# MP3_Shield.net
KiCad netlist of a schematic drawn in EAGLE
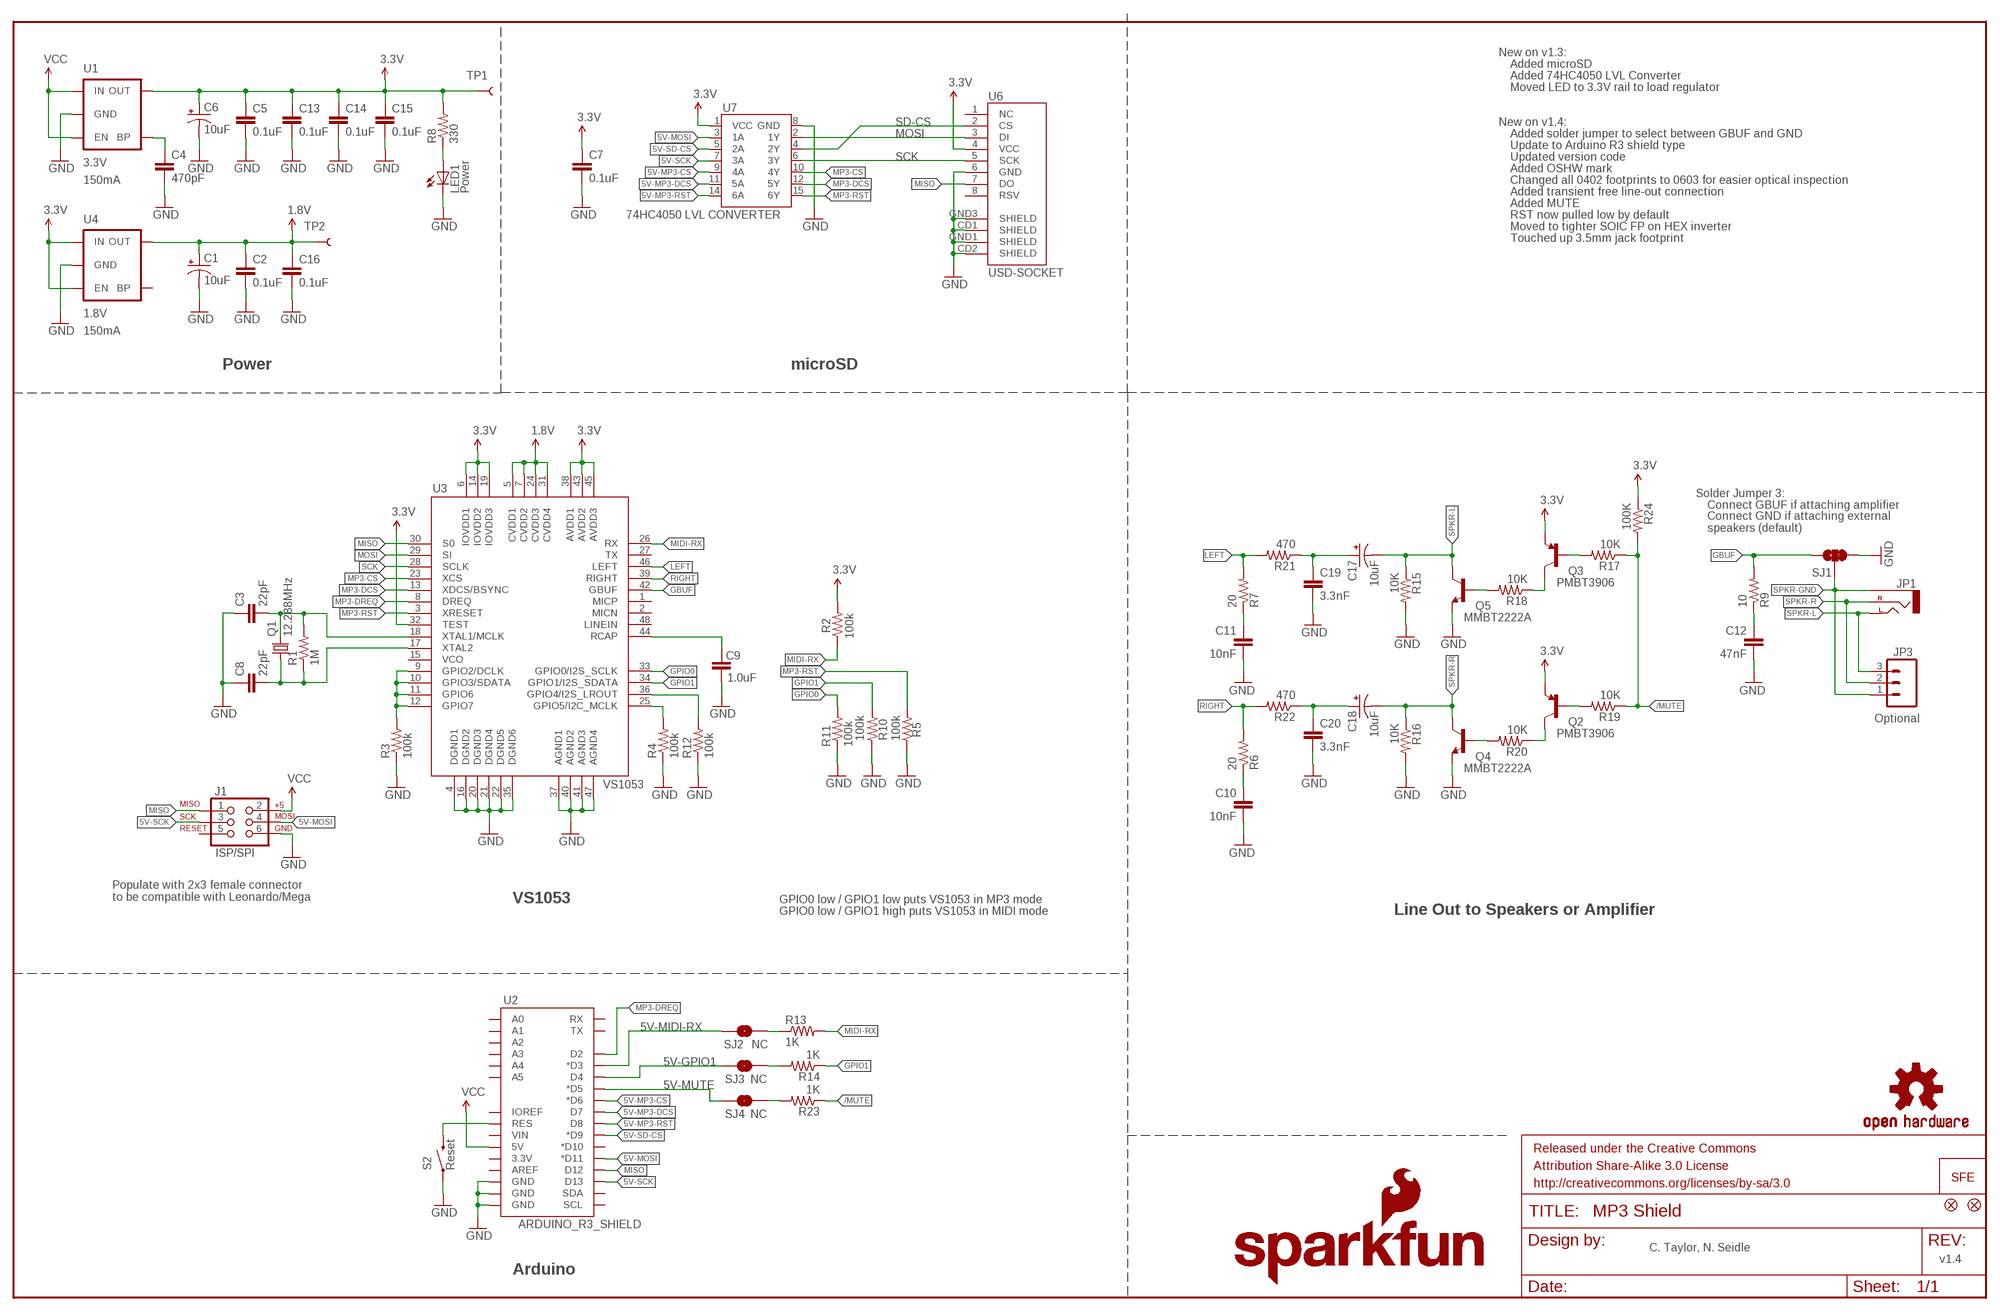
[diagram p0: schematic, sheet 1]

(export (version "E")
  (design (tool "Eeschema 10.0.6"))
  (components
    (comp (ref "C1")
      (value "10uF")
      (footprint "eagle-import:EIA3216")
      (libsource (lib "eagle-import") (part "10UF-16V-10%(TANT)"))
    )
    (comp (ref "C2")
      (value "0.1uF")
      (footprint "eagle-import:0603-CAP")
      (libsource (lib "eagle-import") (part "0.1UF-25V(+80/-20%)(0603)"))
    )
    (comp (ref "C3")
      (value "22pF")
      (footprint "eagle-import:0603-CAP")
      (libsource (lib "eagle-import") (part "22PF-50V-5%(0603)"))
    )
    (comp (ref "C4")
      (value "470pF")
      (footprint "eagle-import:0603-CAP")
      (libsource (lib "eagle-import") (part "470PF-50V-5%(0603)SMD"))
    )
    (comp (ref "C5")
      (value "0.1uF")
      (footprint "eagle-import:0603-CAP")
      (libsource (lib "eagle-import") (part "0.1UF-25V(+80/-20%)(0603)"))
    )
    (comp (ref "C6")
      (value "10uF")
      (footprint "eagle-import:EIA3216")
      (libsource (lib "eagle-import") (part "10UF-16V-10%(TANT)"))
    )
    (comp (ref "C7")
      (value "0.1uF")
      (footprint "eagle-import:0603-CAP")
      (libsource (lib "eagle-import") (part "0.1UF-25V(+80/-20%)(0603)"))
    )
    (comp (ref "C8")
      (value "22pF")
      (footprint "eagle-import:0603-CAP")
      (libsource (lib "eagle-import") (part "22PF-50V-5%(0603)"))
    )
    (comp (ref "C9")
      (value "1.0uF")
      (footprint "eagle-import:0603-CAP")
      (libsource (lib "eagle-import") (part "1.0UF-16V-10%(0603)"))
    )
    (comp (ref "C10")
      (value "10nF")
      (footprint "eagle-import:0603-CAP")
      (libsource (lib "eagle-import") (part "10NF/10000PF-50V-10%(0603)"))
    )
    (comp (ref "C11")
      (value "10nF")
      (footprint "eagle-import:0603-CAP")
      (libsource (lib "eagle-import") (part "10NF/10000PF-50V-10%(0603)"))
    )
    (comp (ref "C12")
      (value "47nF")
      (footprint "eagle-import:0603-CAP")
      (libsource (lib "eagle-import") (part "47NF(0.047UF/47000PF)-25V-5%(0603)SMD"))
    )
    (comp (ref "C13")
      (value "0.1uF")
      (footprint "eagle-import:0603-CAP")
      (libsource (lib "eagle-import") (part "0.1UF-25V(+80/-20%)(0603)"))
    )
    (comp (ref "C14")
      (value "0.1uF")
      (footprint "eagle-import:0603-CAP")
      (libsource (lib "eagle-import") (part "0.1UF-25V(+80/-20%)(0603)"))
    )
    (comp (ref "C15")
      (value "0.1uF")
      (footprint "eagle-import:0603-CAP")
      (libsource (lib "eagle-import") (part "0.1UF-25V(+80/-20%)(0603)"))
    )
    (comp (ref "C16")
      (value "0.1uF")
      (footprint "eagle-import:0603-CAP")
      (libsource (lib "eagle-import") (part "0.1UF-25V(+80/-20%)(0603)"))
    )
    (comp (ref "C17")
      (value "10uF")
      (footprint "eagle-import:EIA3216")
      (libsource (lib "eagle-import") (part "10UF-16V-10%(TANT)"))
    )
    (comp (ref "C18")
      (value "10uF")
      (footprint "eagle-import:EIA3216")
      (libsource (lib "eagle-import") (part "10UF-16V-10%(TANT)"))
    )
    (comp (ref "C19")
      (value "3.3nF")
      (footprint "eagle-import:0603-CAP")
      (libsource (lib "eagle-import") (part "3.3NF-100V-10%(0603)"))
    )
    (comp (ref "C20")
      (value "3.3nF")
      (footprint "eagle-import:0603-CAP")
      (libsource (lib "eagle-import") (part "3.3NF-100V-10%(0603)"))
    )
    (comp (ref "FRAME1")
      (value "FRAME-LEDGER")
      (footprint "eagle-import:CREATIVE_COMMONS")
      (libsource (lib "eagle-import") (part "FRAME-LEDGER"))
    )
    (comp (ref "J1")
      (value "ISP/SPI")
      (footprint "eagle-import:2X3")
      (libsource (lib "eagle-import") (part "AVR_SPI_PRG_6PTH"))
    )
    (comp (ref "JP1")
      (value "AUDIO-JACKSMD2")
      (footprint "eagle-import:AUDIO-JACK-3.5MM-SMD")
      (libsource (lib "eagle-import") (part "AUDIO-JACKSMD2"))
    )
    (comp (ref "JP3")
      (value "Optional")
      (footprint "eagle-import:1X03")
      (libsource (lib "eagle-import") (part "M03PTH"))
    )
    (comp (ref "LED1")
      (value "Power")
      (footprint "eagle-import:LED-0603")
      (libsource (lib "eagle-import") (part "LED-RED0603"))
    )
    (comp (ref "LOGO1")
      (value "OSHW-LOGOS")
      (footprint "eagle-import:OSHW-LOGO-S")
      (libsource (lib "eagle-import") (part "OSHW-LOGOS"))
    )
    (comp (ref "LOGO2")
      (value "SFE_LOGO_NAME_FLAME.1_INCH")
      (footprint "eagle-import:SFE_LOGO_NAME_FLAME_.1")
      (libsource (lib "eagle-import") (part "SFE_LOGO_NAME_FLAME.1_INCH"))
    )
    (comp (ref "Q1")
      (value "12.288MHz")
      (footprint "eagle-import:CRYSTAL-SMD-5X3")
      (libsource (lib "eagle-import") (part "CRYSTAL5X3"))
    )
    (comp (ref "Q2")
      (value "PMBT3906")
      (footprint "eagle-import:SOT23-3")
      (libsource (lib "eagle-import") (part "TRANSISTOR_PNPPMBT3906"))
    )
    (comp (ref "Q3")
      (value "PMBT3906")
      (footprint "eagle-import:SOT23-3")
      (libsource (lib "eagle-import") (part "TRANSISTOR_PNPPMBT3906"))
    )
    (comp (ref "Q4")
      (value "MMBT2222A")
      (footprint "eagle-import:SOT23-3")
      (libsource (lib "eagle-import") (part "TRANSISTOR_NPNMMBT2222A"))
    )
    (comp (ref "Q5")
      (value "MMBT2222A")
      (footprint "eagle-import:SOT23-3")
      (libsource (lib "eagle-import") (part "TRANSISTOR_NPNMMBT2222A"))
    )
    (comp (ref "R1")
      (value "1M")
      (footprint "eagle-import:0603-RES")
      (libsource (lib "eagle-import") (part "1M-1%"))
    )
    (comp (ref "R2")
      (value "100k")
      (footprint "eagle-import:0603-RES")
      (libsource (lib "eagle-import") (part "100KOHM1/10W1%(0603)"))
    )
    (comp (ref "R3")
      (value "100k")
      (footprint "eagle-import:0603-RES")
      (libsource (lib "eagle-import") (part "100KOHM1/10W1%(0603)"))
    )
    (comp (ref "R4")
      (value "100k")
      (footprint "eagle-import:0603-RES")
      (libsource (lib "eagle-import") (part "100KOHM1/10W1%(0603)"))
    )
    (comp (ref "R5")
      (value "100k")
      (footprint "eagle-import:0603-RES")
      (libsource (lib "eagle-import") (part "100KOHM1/10W1%(0603)"))
    )
    (comp (ref "R6")
      (value "20")
      (footprint "eagle-import:0603-RES")
      (libsource (lib "eagle-import") (part "20OHM1/10W1%(0603)SMD"))
    )
    (comp (ref "R7")
      (value "20")
      (footprint "eagle-import:0603-RES")
      (libsource (lib "eagle-import") (part "20OHM1/10W1%(0603)SMD"))
    )
    (comp (ref "R8")
      (value "330")
      (footprint "eagle-import:0603-RES")
      (libsource (lib "eagle-import") (part "330OHM1/10W1%(0603)"))
    )
    (comp (ref "R9")
      (value "10")
      (footprint "eagle-import:0603-RES")
      (libsource (lib "eagle-import") (part "10OHM1/10W5%0603SMD"))
    )
    (comp (ref "R10")
      (value "100k")
      (footprint "eagle-import:0603-RES")
      (libsource (lib "eagle-import") (part "100KOHM1/10W1%(0603)"))
    )
    (comp (ref "R11")
      (value "100k")
      (footprint "eagle-import:0603-RES")
      (libsource (lib "eagle-import") (part "100KOHM1/10W1%(0603)"))
    )
    (comp (ref "R12")
      (value "100k")
      (footprint "eagle-import:0603-RES")
      (libsource (lib "eagle-import") (part "100KOHM1/10W1%(0603)"))
    )
    (comp (ref "R13")
      (value "1K")
      (footprint "eagle-import:0603-RES")
      (libsource (lib "eagle-import") (part "1KOHM1/10W1%(0603)"))
    )
    (comp (ref "R14")
      (value "1K")
      (footprint "eagle-import:0603-RES")
      (libsource (lib "eagle-import") (part "1KOHM1/10W1%(0603)"))
    )
    (comp (ref "R15")
      (value "10K")
      (footprint "eagle-import:0603-RES")
      (libsource (lib "eagle-import") (part "10KOHM1/10W1%(0603)0603"))
    )
    (comp (ref "R16")
      (value "10K")
      (footprint "eagle-import:0603-RES")
      (libsource (lib "eagle-import") (part "10KOHM1/10W1%(0603)0603"))
    )
    (comp (ref "R17")
      (value "10K")
      (footprint "eagle-import:0603-RES")
      (libsource (lib "eagle-import") (part "10KOHM1/10W1%(0603)0603"))
    )
    (comp (ref "R18")
      (value "10K")
      (footprint "eagle-import:0603-RES")
      (libsource (lib "eagle-import") (part "10KOHM1/10W1%(0603)0603"))
    )
    (comp (ref "R19")
      (value "10K")
      (footprint "eagle-import:0603-RES")
      (libsource (lib "eagle-import") (part "10KOHM1/10W1%(0603)0603"))
    )
    (comp (ref "R20")
      (value "10K")
      (footprint "eagle-import:0603-RES")
      (libsource (lib "eagle-import") (part "10KOHM1/10W1%(0603)0603"))
    )
    (comp (ref "R21")
      (value "470")
      (footprint "eagle-import:0603-RES")
      (libsource (lib "eagle-import") (part "470OHM1/10W1%(0603)"))
    )
    (comp (ref "R22")
      (value "470")
      (footprint "eagle-import:0603-RES")
      (libsource (lib "eagle-import") (part "470OHM1/10W1%(0603)"))
    )
    (comp (ref "R23")
      (value "1K")
      (footprint "eagle-import:0603-RES")
      (libsource (lib "eagle-import") (part "1KOHM1/10W1%(0603)"))
    )
    (comp (ref "R24")
      (value "100K")
      (footprint "eagle-import:0603-RES")
      (libsource (lib "eagle-import") (part "100KOHM1/10W1%(0603)"))
    )
    (comp (ref "S2")
      (value "Reset")
      (footprint "eagle-import:TACTILE_SWITCH_SMD")
      (libsource (lib "eagle-import") (part "SWITCH-MOMENTARY-2SMD"))
    )
    (comp (ref "SJ1")
      (value "SOLDERJUMPER_2WAYPASTE2&3")
      (footprint "eagle-import:SJ_3_PASTE2&3")
      (libsource (lib "eagle-import") (part "SOLDERJUMPER_2WAYPASTE2&3"))
    )
    (comp (ref "SJ2")
      (value "NC")
      (footprint "eagle-import:SJ_2S-TRACE")
      (libsource (lib "eagle-import") (part "SOLDERJUMPERTRACE"))
    )
    (comp (ref "SJ3")
      (value "NC")
      (footprint "eagle-import:SJ_2S-TRACE")
      (libsource (lib "eagle-import") (part "SOLDERJUMPERTRACE"))
    )
    (comp (ref "SJ4")
      (value "NC")
      (footprint "eagle-import:SJ_2S-TRACE")
      (libsource (lib "eagle-import") (part "SOLDERJUMPERTRACE"))
    )
    (comp (ref "TP1")
      (value "TEST-POINT3X5")
      (footprint "eagle-import:PAD.03X.05")
      (libsource (lib "eagle-import") (part "TEST-POINT3X5"))
    )
    (comp (ref "TP2")
      (value "TEST-POINT3X5")
      (footprint "eagle-import:PAD.03X.05")
      (libsource (lib "eagle-import") (part "TEST-POINT3X5"))
    )
    (comp (ref "U$4")
      (value "FIDUCIAL1X2")
      (footprint "eagle-import:FIDUCIAL-1X2")
      (libsource (lib "eagle-import") (part "FIDUCIAL1X2"))
    )
    (comp (ref "U$5")
      (value "FIDUCIAL1X2")
      (footprint "eagle-import:FIDUCIAL-1X2")
      (libsource (lib "eagle-import") (part "FIDUCIAL1X2"))
    )
    (comp (ref "U$8")
      (value "LOGO-SFENEW")
      (footprint "eagle-import:SFE-NEW-WEBLOGO")
      (libsource (lib "eagle-import") (part "LOGO-SFENEW"))
    )
    (comp (ref "U1")
      (value "3.3V")
      (footprint "eagle-import:SOT23-5")
      (libsource (lib "eagle-import") (part "V_REG_MIC52053.3V"))
    )
    (comp (ref "U2")
      (value "ARDUINO_R3_SHIELD")
      (footprint "eagle-import:UNO_R3_SHIELD")
      (libsource (lib "eagle-import") (part "ARDUINO_R3_SHIELD"))
    )
    (comp (ref "U3")
      (value "VS1053")
      (footprint "eagle-import:LQFP-48")
      (libsource (lib "eagle-import") (part "VS1033/1053SMD"))
    )
    (comp (ref "U4")
      (value "1.8V")
      (footprint "eagle-import:SC70")
      (libsource (lib "eagle-import") (part "V_REG_SP62141.8V"))
    )
    (comp (ref "U6")
      (value "USD-SOCKET")
      (footprint "eagle-import:MICRO-SD-SOCKET-PP")
      (libsource (lib "eagle-import") (part "USD-SOCKETNEW"))
    )
    (comp (ref "U7")
      (value "74HC4050 LVL CONVERTER")
      (footprint "eagle-import:SO016")
      (libsource (lib "eagle-import") (part "HEX_CONVERTER"))
    )
  )
  (nets
    (net (code "1") (name "/5V-GPIO1") (class "Default")
      (node (ref "SJ3") (pin "2") (pinfunction "2_2") (pintype "passive"))
      (node (ref "U2") (pin "D4") (pinfunction "D4_D4") (pintype "bidirectional"))
    )
    (net (code "2") (name "/5V-MIDI-RX") (class "Default")
      (node (ref "SJ2") (pin "1") (pinfunction "1_1") (pintype "passive"))
      (node (ref "U2") (pin "D3") (pinfunction "*D3_D3") (pintype "bidirectional"))
    )
    (net (code "3") (name "/5V-MUTE") (class "Default")
      (node (ref "SJ4") (pin "2") (pinfunction "2_2") (pintype "passive"))
      (node (ref "U2") (pin "D5") (pinfunction "*D5_D5") (pintype "bidirectional"))
    )
    (net (code "4") (name "/SD-CS") (class "Default")
      (node (ref "U6") (pin "2") (pinfunction "CS_2") (pintype "bidirectional"))
      (node (ref "U7") (pin "4") (pinfunction "2Y_4") (pintype "bidirectional"))
    )
    (net (code "5") (name "1.8V") (class "Default")
      (node (ref "C1") (pin "A") (pinfunction "+_A") (pintype "passive"))
      (node (ref "C16") (pin "1") (pinfunction "1_1") (pintype "passive"))
      (node (ref "C2") (pin "1") (pinfunction "1_1") (pintype "passive"))
      (node (ref "TP2") (pin "P$1") (pinfunction "1_P$1") (pintype "bidirectional"))
      (node (ref "U3") (pin "24") (pinfunction "CVDD3_24") (pintype "bidirectional"))
      (node (ref "U3") (pin "31") (pinfunction "CVDD4_31") (pintype "bidirectional"))
      (node (ref "U3") (pin "5") (pinfunction "CVDD1_5") (pintype "bidirectional"))
      (node (ref "U3") (pin "7") (pinfunction "CVDD2_7") (pintype "bidirectional"))
      (node (ref "U4") (pin "5") (pinfunction "OUT_5") (pintype "passive"))
    )
    (net (code "6") (name "3.3V") (class "Default")
      (node (ref "C13") (pin "1") (pinfunction "1_1") (pintype "passive"))
      (node (ref "C14") (pin "1") (pinfunction "1_1") (pintype "passive"))
      (node (ref "C15") (pin "1") (pinfunction "1_1") (pintype "passive"))
      (node (ref "C5") (pin "1") (pinfunction "1_1") (pintype "passive"))
      (node (ref "C6") (pin "A") (pinfunction "+_A") (pintype "passive"))
      (node (ref "C7") (pin "1") (pinfunction "1_1") (pintype "passive"))
      (node (ref "Q2") (pin "2") (pinfunction "E_2") (pintype "passive"))
      (node (ref "Q3") (pin "2") (pinfunction "E_2") (pintype "passive"))
      (node (ref "R2") (pin "2") (pinfunction "2_2") (pintype "passive"))
      (node (ref "R24") (pin "1") (pinfunction "1_1") (pintype "passive"))
      (node (ref "R8") (pin "2") (pinfunction "2_2") (pintype "passive"))
      (node (ref "TP1") (pin "P$1") (pinfunction "1_P$1") (pintype "bidirectional"))
      (node (ref "U1") (pin "5") (pinfunction "OUT_5") (pintype "passive"))
      (node (ref "U3") (pin "14") (pinfunction "IOVDD2_14") (pintype "bidirectional"))
      (node (ref "U3") (pin "19") (pinfunction "IOVDD3_19") (pintype "bidirectional"))
      (node (ref "U3") (pin "32") (pinfunction "TEST_32") (pintype "bidirectional"))
      (node (ref "U3") (pin "38") (pinfunction "AVDD1_38") (pintype "bidirectional"))
      (node (ref "U3") (pin "43") (pinfunction "AVDD2_43") (pintype "bidirectional"))
      (node (ref "U3") (pin "45") (pinfunction "AVDD3_45") (pintype "bidirectional"))
      (node (ref "U3") (pin "6") (pinfunction "IOVDD1_6") (pintype "bidirectional"))
      (node (ref "U4") (pin "1") (pinfunction "IN_1") (pintype "input"))
      (node (ref "U4") (pin "3") (pinfunction "EN_3") (pintype "input"))
      (node (ref "U6") (pin "4") (pinfunction "VCC_4") (pintype "bidirectional"))
      (node (ref "U7") (pin "1") (pinfunction "VCC_1") (pintype "bidirectional"))
    )
    (net (code "7") (name "5V-MOSI") (class "Default")
      (node (ref "J1") (pin "4") (pinfunction "4_4") (pintype "passive"))
      (node (ref "U2") (pin "D11") (pinfunction "*D11_D11") (pintype "bidirectional"))
      (node (ref "U7") (pin "3") (pinfunction "1A_3") (pintype "bidirectional"))
    )
    (net (code "8") (name "5V-MP3-CS") (class "Default")
      (node (ref "U2") (pin "D6") (pinfunction "*D6_D6") (pintype "bidirectional"))
      (node (ref "U7") (pin "9") (pinfunction "4A_9") (pintype "bidirectional"))
    )
    (net (code "9") (name "5V-MP3-DCS") (class "Default")
      (node (ref "U2") (pin "D7") (pinfunction "D7_D7") (pintype "bidirectional"))
      (node (ref "U7") (pin "11") (pinfunction "5A_11") (pintype "bidirectional"))
    )
    (net (code "10") (name "5V-MP3-RST") (class "Default")
      (node (ref "U2") (pin "D8") (pinfunction "D8_D8") (pintype "bidirectional"))
      (node (ref "U7") (pin "14") (pinfunction "6A_14") (pintype "bidirectional"))
    )
    (net (code "11") (name "5V-SCK") (class "Default")
      (node (ref "J1") (pin "3") (pinfunction "3_3") (pintype "passive"))
      (node (ref "U2") (pin "D13") (pinfunction "D13_D13") (pintype "bidirectional"))
      (node (ref "U7") (pin "7") (pinfunction "3A_7") (pintype "bidirectional"))
    )
    (net (code "12") (name "5V-SD-CS") (class "Default")
      (node (ref "U2") (pin "D9") (pinfunction "*D9_D9") (pintype "bidirectional"))
      (node (ref "U7") (pin "5") (pinfunction "2A_5") (pintype "bidirectional"))
    )
    (net (code "13") (name "GBUF") (class "Default")
      (node (ref "R9") (pin "2") (pinfunction "2_2") (pintype "passive"))
      (node (ref "SJ1") (pin "1") (pinfunction "1_1") (pintype "passive"))
      (node (ref "U3") (pin "42") (pinfunction "GBUF_42") (pintype "bidirectional"))
    )
    (net (code "14") (name "GND") (class "Default")
      (node (ref "C1") (pin "C") (pinfunction "-_C") (pintype "passive"))
      (node (ref "C10") (pin "2") (pinfunction "2_2") (pintype "passive"))
      (node (ref "C11") (pin "2") (pinfunction "2_2") (pintype "passive"))
      (node (ref "C12") (pin "2") (pinfunction "2_2") (pintype "passive"))
      (node (ref "C13") (pin "2") (pinfunction "2_2") (pintype "passive"))
      (node (ref "C14") (pin "2") (pinfunction "2_2") (pintype "passive"))
      (node (ref "C15") (pin "2") (pinfunction "2_2") (pintype "passive"))
      (node (ref "C16") (pin "2") (pinfunction "2_2") (pintype "passive"))
      (node (ref "C19") (pin "2") (pinfunction "2_2") (pintype "passive"))
      (node (ref "C2") (pin "2") (pinfunction "2_2") (pintype "passive"))
      (node (ref "C20") (pin "2") (pinfunction "2_2") (pintype "passive"))
      (node (ref "C3") (pin "1") (pinfunction "1_1") (pintype "passive"))
      (node (ref "C4") (pin "2") (pinfunction "2_2") (pintype "passive"))
      (node (ref "C5") (pin "2") (pinfunction "2_2") (pintype "passive"))
      (node (ref "C6") (pin "C") (pinfunction "-_C") (pintype "passive"))
      (node (ref "C7") (pin "2") (pinfunction "2_2") (pintype "passive"))
      (node (ref "C8") (pin "1") (pinfunction "1_1") (pintype "passive"))
      (node (ref "C9") (pin "1") (pinfunction "1_1") (pintype "passive"))
      (node (ref "J1") (pin "6") (pinfunction "6_6") (pintype "passive"))
      (node (ref "LED1") (pin "C") (pinfunction "C_C") (pintype "passive"))
      (node (ref "Q4") (pin "2") (pinfunction "E_2") (pintype "passive"))
      (node (ref "Q5") (pin "2") (pinfunction "E_2") (pintype "passive"))
      (node (ref "R10") (pin "1") (pinfunction "1_1") (pintype "passive"))
      (node (ref "R11") (pin "1") (pinfunction "1_1") (pintype "passive"))
      (node (ref "R12") (pin "1") (pinfunction "1_1") (pintype "passive"))
      (node (ref "R15") (pin "2") (pinfunction "2_2") (pintype "passive"))
      (node (ref "R16") (pin "2") (pinfunction "2_2") (pintype "passive"))
      (node (ref "R3") (pin "1") (pinfunction "1_1") (pintype "passive"))
      (node (ref "R4") (pin "1") (pinfunction "1_1") (pintype "passive"))
      (node (ref "R5") (pin "1") (pinfunction "1_1") (pintype "passive"))
      (node (ref "S2") (pin "1") (pinfunction "1_1") (pintype "passive"))
      (node (ref "SJ1") (pin "3") (pinfunction "3_3") (pintype "passive"))
      (node (ref "U1") (pin "2") (pinfunction "GND_2") (pintype "input"))
      (node (ref "U2") (pin "GND@0") (pinfunction "GND_GND@0") (pintype "bidirectional"))
      (node (ref "U2") (pin "GND@1") (pinfunction "GND_GND@1") (pintype "bidirectional"))
      (node (ref "U2") (pin "GND@2") (pinfunction "GND_GND@2") (pintype "bidirectional"))
      (node (ref "U3") (pin "16") (pinfunction "DGND2_16") (pintype "bidirectional"))
      (node (ref "U3") (pin "20") (pinfunction "DGND3_20") (pintype "bidirectional"))
      (node (ref "U3") (pin "21") (pinfunction "DGND4_21") (pintype "bidirectional"))
      (node (ref "U3") (pin "22") (pinfunction "DGND5_22") (pintype "bidirectional"))
      (node (ref "U3") (pin "35") (pinfunction "DGND6_35") (pintype "bidirectional"))
      (node (ref "U3") (pin "37") (pinfunction "AGND1_37") (pintype "bidirectional"))
      (node (ref "U3") (pin "4") (pinfunction "DGND1_4") (pintype "bidirectional"))
      (node (ref "U3") (pin "40") (pinfunction "AGND2_40") (pintype "bidirectional"))
      (node (ref "U3") (pin "41") (pinfunction "AGND3_41") (pintype "bidirectional"))
      (node (ref "U3") (pin "47") (pinfunction "AGND4_47") (pintype "bidirectional"))
      (node (ref "U4") (pin "2") (pinfunction "GND_2") (pintype "input"))
      (node (ref "U6") (pin "6") (pinfunction "GND_6") (pintype "bidirectional"))
      (node (ref "U6") (pin "CD1") (pinfunction "SHIELD_CD1") (pintype "bidirectional"))
      (node (ref "U6") (pin "CD2") (pinfunction "SHIELD_CD2") (pintype "bidirectional"))
      (node (ref "U6") (pin "GND1") (pinfunction "SHIELD_GND1") (pintype "bidirectional"))
      (node (ref "U6") (pin "GND3") (pinfunction "SHIELD_GND3") (pintype "bidirectional"))
      (node (ref "U7") (pin "8") (pinfunction "GND_8") (pintype "bidirectional"))
    )
    (net (code "15") (name "GPIO0") (class "Default")
      (node (ref "R11") (pin "2") (pinfunction "2_2") (pintype "passive"))
      (node (ref "U3") (pin "33") (pinfunction "GPIO0/I2S_SCLK_33") (pintype "bidirectional"))
    )
    (net (code "16") (name "GPIO1") (class "Default")
      (node (ref "R10") (pin "2") (pinfunction "2_2") (pintype "passive"))
      (node (ref "R14") (pin "1") (pinfunction "1_1") (pintype "passive"))
      (node (ref "U3") (pin "34") (pinfunction "GPIO1/I2S_SDATA_34") (pintype "bidirectional"))
    )
    (net (code "17") (name "LEFT") (class "Default")
      (node (ref "R21") (pin "2") (pinfunction "2_2") (pintype "passive"))
      (node (ref "R7") (pin "2") (pinfunction "2_2") (pintype "passive"))
      (node (ref "U3") (pin "46") (pinfunction "LEFT_46") (pintype "bidirectional"))
    )
    (net (code "18") (name "MIDI-RX") (class "Default")
      (node (ref "R13") (pin "2") (pinfunction "2_2") (pintype "passive"))
      (node (ref "R2") (pin "1") (pinfunction "1_1") (pintype "passive"))
      (node (ref "U3") (pin "26") (pinfunction "RX_26") (pintype "bidirectional"))
    )
    (net (code "19") (name "MISO") (class "Default")
      (node (ref "J1") (pin "1") (pinfunction "1_1") (pintype "passive"))
      (node (ref "U2") (pin "D12") (pinfunction "D12_D12") (pintype "bidirectional"))
      (node (ref "U3") (pin "30") (pinfunction "S0_30") (pintype "bidirectional"))
      (node (ref "U6") (pin "7") (pinfunction "DO_7") (pintype "bidirectional"))
    )
    (net (code "20") (name "MOSI") (class "Default")
      (node (ref "U3") (pin "29") (pinfunction "SI_29") (pintype "bidirectional"))
      (node (ref "U6") (pin "3") (pinfunction "DI_3") (pintype "bidirectional"))
      (node (ref "U7") (pin "2") (pinfunction "1Y_2") (pintype "bidirectional"))
    )
    (net (code "21") (name "MP3-CS") (class "Default")
      (node (ref "U3") (pin "23") (pinfunction "XCS_23") (pintype "bidirectional"))
      (node (ref "U7") (pin "10") (pinfunction "4Y_10") (pintype "bidirectional"))
    )
    (net (code "22") (name "MP3-DCS") (class "Default")
      (node (ref "U3") (pin "13") (pinfunction "XDCS/BSYNC_13") (pintype "bidirectional"))
      (node (ref "U7") (pin "12") (pinfunction "5Y_12") (pintype "bidirectional"))
    )
    (net (code "23") (name "MP3-DREQ") (class "Default")
      (node (ref "U2") (pin "D2") (pinfunction "D2_D2") (pintype "bidirectional"))
      (node (ref "U3") (pin "8") (pinfunction "DREQ_8") (pintype "bidirectional"))
    )
    (net (code "24") (name "MP3-RST") (class "Default")
      (node (ref "R5") (pin "2") (pinfunction "2_2") (pintype "passive"))
      (node (ref "U3") (pin "3") (pinfunction "XRESET_3") (pintype "bidirectional"))
      (node (ref "U7") (pin "15") (pinfunction "6Y_15") (pintype "bidirectional"))
    )
    (net (code "25") (name "Net-(C10-Pad1)") (class "Default")
      (node (ref "C10") (pin "1") (pinfunction "1_1") (pintype "passive"))
      (node (ref "R6") (pin "1") (pinfunction "1_1") (pintype "passive"))
    )
    (net (code "26") (name "Net-(C11-Pad1)") (class "Default")
      (node (ref "C11") (pin "1") (pinfunction "1_1") (pintype "passive"))
      (node (ref "R7") (pin "1") (pinfunction "1_1") (pintype "passive"))
    )
    (net (code "27") (name "Net-(C12-Pad1)") (class "Default")
      (node (ref "C12") (pin "1") (pinfunction "1_1") (pintype "passive"))
      (node (ref "R9") (pin "1") (pinfunction "1_1") (pintype "passive"))
    )
    (net (code "28") (name "Net-(C17-+)") (class "Default")
      (node (ref "C17") (pin "A") (pinfunction "+_A") (pintype "passive"))
      (node (ref "C19") (pin "1") (pinfunction "1_1") (pintype "passive"))
      (node (ref "R21") (pin "1") (pinfunction "1_1") (pintype "passive"))
    )
    (net (code "29") (name "Net-(C18-+)") (class "Default")
      (node (ref "C18") (pin "A") (pinfunction "+_A") (pintype "passive"))
      (node (ref "C20") (pin "1") (pinfunction "1_1") (pintype "passive"))
      (node (ref "R22") (pin "1") (pinfunction "1_1") (pintype "passive"))
    )
    (net (code "30") (name "Net-(LED1-PadA)") (class "Default")
      (node (ref "LED1") (pin "A") (pinfunction "A_A") (pintype "passive"))
      (node (ref "R8") (pin "1") (pinfunction "1_1") (pintype "passive"))
    )
    (net (code "31") (name "Net-(Q1-2)") (class "Default")
      (node (ref "C3") (pin "2") (pinfunction "2_2") (pintype "passive"))
      (node (ref "Q1") (pin "3") (pinfunction "2_3") (pintype "passive"))
      (node (ref "R1") (pin "2") (pinfunction "2_2") (pintype "passive"))
      (node (ref "U3") (pin "18") (pinfunction "XTAL1/MCLK_18") (pintype "bidirectional"))
    )
    (net (code "32") (name "Net-(Q2-B)") (class "Default")
      (node (ref "Q2") (pin "1") (pinfunction "B_1") (pintype "passive"))
      (node (ref "R19") (pin "2") (pinfunction "2_2") (pintype "passive"))
    )
    (net (code "33") (name "Net-(Q2-C)") (class "Default")
      (node (ref "Q2") (pin "3") (pinfunction "C_3") (pintype "passive"))
      (node (ref "R20") (pin "1") (pinfunction "1_1") (pintype "passive"))
    )
    (net (code "34") (name "Net-(Q3-B)") (class "Default")
      (node (ref "Q3") (pin "1") (pinfunction "B_1") (pintype "passive"))
      (node (ref "R17") (pin "2") (pinfunction "2_2") (pintype "passive"))
    )
    (net (code "35") (name "Net-(Q3-C)") (class "Default")
      (node (ref "Q3") (pin "3") (pinfunction "C_3") (pintype "passive"))
      (node (ref "R18") (pin "1") (pinfunction "1_1") (pintype "passive"))
    )
    (net (code "36") (name "Net-(Q4-B)") (class "Default")
      (node (ref "Q4") (pin "1") (pinfunction "B_1") (pintype "passive"))
      (node (ref "R20") (pin "2") (pinfunction "2_2") (pintype "passive"))
    )
    (net (code "37") (name "Net-(Q5-B)") (class "Default")
      (node (ref "Q5") (pin "1") (pinfunction "B_1") (pintype "passive"))
      (node (ref "R18") (pin "2") (pinfunction "2_2") (pintype "passive"))
    )
    (net (code "38") (name "Net-(R13-Pad1)") (class "Default")
      (node (ref "R13") (pin "1") (pinfunction "1_1") (pintype "passive"))
      (node (ref "SJ2") (pin "2") (pinfunction "2_2") (pintype "passive"))
    )
    (net (code "39") (name "Net-(R14-Pad2)") (class "Default")
      (node (ref "R14") (pin "2") (pinfunction "2_2") (pintype "passive"))
      (node (ref "SJ3") (pin "1") (pinfunction "1_1") (pintype "passive"))
    )
    (net (code "40") (name "Net-(R23-Pad2)") (class "Default")
      (node (ref "R23") (pin "2") (pinfunction "2_2") (pintype "passive"))
      (node (ref "SJ4") (pin "1") (pinfunction "1_1") (pintype "passive"))
    )
    (net (code "41") (name "Net-(S2-2)") (class "Default")
      (node (ref "S2") (pin "3") (pinfunction "2_3") (pintype "passive"))
      (node (ref "U2") (pin "RES") (pinfunction "RES_RES") (pintype "bidirectional"))
    )
    (net (code "42") (name "Net-(U1-BP)") (class "Default")
      (node (ref "C4") (pin "1") (pinfunction "1_1") (pintype "passive"))
      (node (ref "U1") (pin "4") (pinfunction "BP_4") (pintype "input"))
    )
    (net (code "43") (name "Net-(U3-GPIO2{slash}DCLK)") (class "Default")
      (node (ref "R3") (pin "2") (pinfunction "2_2") (pintype "passive"))
      (node (ref "U3") (pin "10") (pinfunction "GPIO3/SDATA_10") (pintype "bidirectional"))
      (node (ref "U3") (pin "11") (pinfunction "GPIO6_11") (pintype "bidirectional"))
      (node (ref "U3") (pin "12") (pinfunction "GPIO7_12") (pintype "bidirectional"))
      (node (ref "U3") (pin "9") (pinfunction "GPIO2/DCLK_9") (pintype "bidirectional"))
    )
    (net (code "44") (name "Net-(U3-GPIO4{slash}I2S_LROUT)") (class "Default")
      (node (ref "R12") (pin "2") (pinfunction "2_2") (pintype "passive"))
      (node (ref "U3") (pin "36") (pinfunction "GPIO4/I2S_LROUT_36") (pintype "bidirectional"))
    )
    (net (code "45") (name "Net-(U3-GPIO5{slash}I2C_MCLK)") (class "Default")
      (node (ref "R4") (pin "2") (pinfunction "2_2") (pintype "passive"))
      (node (ref "U3") (pin "25") (pinfunction "GPIO5/I2C_MCLK_25") (pintype "bidirectional"))
    )
    (net (code "46") (name "Net-(U3-RCAP)") (class "Default")
      (node (ref "C9") (pin "2") (pinfunction "2_2") (pintype "passive"))
      (node (ref "U3") (pin "44") (pinfunction "RCAP_44") (pintype "bidirectional"))
    )
    (net (code "47") (name "Net-(U3-XTAL2)") (class "Default")
      (node (ref "C8") (pin "2") (pinfunction "2_2") (pintype "passive"))
      (node (ref "Q1") (pin "1") (pinfunction "1_1") (pintype "passive"))
      (node (ref "R1") (pin "1") (pinfunction "1_1") (pintype "passive"))
      (node (ref "U3") (pin "17") (pinfunction "XTAL2_17") (pintype "bidirectional"))
    )
    (net (code "48") (name "RIGHT") (class "Default")
      (node (ref "R22") (pin "2") (pinfunction "2_2") (pintype "passive"))
      (node (ref "R6") (pin "2") (pinfunction "2_2") (pintype "passive"))
      (node (ref "U3") (pin "39") (pinfunction "RIGHT_39") (pintype "bidirectional"))
    )
    (net (code "49") (name "SCK") (class "Default")
      (node (ref "U3") (pin "28") (pinfunction "SCLK_28") (pintype "bidirectional"))
      (node (ref "U6") (pin "5") (pinfunction "SCK_5") (pintype "bidirectional"))
      (node (ref "U7") (pin "6") (pinfunction "3Y_6") (pintype "bidirectional"))
    )
    (net (code "50") (name "SPKR-GND") (class "Default")
      (node (ref "JP1") (pin "SLEEVE") (pinfunction "SLEEVE_SLEEVE") (pintype "bidirectional"))
      (node (ref "JP3") (pin "1") (pinfunction "1_1") (pintype "passive"))
      (node (ref "SJ1") (pin "2") (pinfunction "2_2") (pintype "passive"))
    )
    (net (code "51") (name "SPKR-L") (class "Default")
      (node (ref "C17") (pin "C") (pinfunction "-_C") (pintype "passive"))
      (node (ref "JP1") (pin "TIP") (pinfunction "LEFT_TIP") (pintype "bidirectional"))
      (node (ref "JP3") (pin "3") (pinfunction "3_3") (pintype "passive"))
      (node (ref "Q5") (pin "3") (pinfunction "C_3") (pintype "passive"))
      (node (ref "R15") (pin "1") (pinfunction "1_1") (pintype "passive"))
    )
    (net (code "52") (name "SPKR-R") (class "Default")
      (node (ref "C18") (pin "C") (pinfunction "-_C") (pintype "passive"))
      (node (ref "JP1") (pin "RING") (pinfunction "RIGHT_RING") (pintype "bidirectional"))
      (node (ref "JP3") (pin "2") (pinfunction "2_2") (pintype "passive"))
      (node (ref "Q4") (pin "3") (pinfunction "C_3") (pintype "passive"))
      (node (ref "R16") (pin "1") (pinfunction "1_1") (pintype "passive"))
    )
    (net (code "53") (name "VCC") (class "Default")
      (node (ref "J1") (pin "2") (pinfunction "2_2") (pintype "passive"))
      (node (ref "U1") (pin "1") (pinfunction "IN_1") (pintype "input"))
      (node (ref "U1") (pin "3") (pinfunction "EN_3") (pintype "input"))
      (node (ref "U2") (pin "5V") (pinfunction "5V_5V") (pintype "bidirectional"))
    )
    (net (code "54") (name "unconnected-(J1-Pad5)") (class "Default")
      (node (ref "J1") (pin "5") (pinfunction "5_5") (pintype "passive"))
    )
    (net (code "55") (name "unconnected-(U2-*D10-PadD10)") (class "Default")
      (node (ref "U2") (pin "D10") (pinfunction "*D10_D10") (pintype "bidirectional"))
    )
    (net (code "56") (name "unconnected-(U2-Pad3.3V)") (class "Default")
      (node (ref "U2") (pin "3.3V") (pinfunction "3.3V_3.3V") (pintype "bidirectional"))
    )
    (net (code "57") (name "unconnected-(U2-PadA0)") (class "Default")
      (node (ref "U2") (pin "A0") (pinfunction "A0_A0") (pintype "bidirectional"))
    )
    (net (code "58") (name "unconnected-(U2-PadA1)") (class "Default")
      (node (ref "U2") (pin "A1") (pinfunction "A1_A1") (pintype "bidirectional"))
    )
    (net (code "59") (name "unconnected-(U2-PadA2)") (class "Default")
      (node (ref "U2") (pin "A2") (pinfunction "A2_A2") (pintype "bidirectional"))
    )
    (net (code "60") (name "unconnected-(U2-PadA3)") (class "Default")
      (node (ref "U2") (pin "A3") (pinfunction "A3_A3") (pintype "bidirectional"))
    )
    (net (code "61") (name "unconnected-(U2-PadA4)") (class "Default")
      (node (ref "U2") (pin "A4") (pinfunction "A4_A4") (pintype "bidirectional"))
    )
    (net (code "62") (name "unconnected-(U2-PadA5)") (class "Default")
      (node (ref "U2") (pin "A5") (pinfunction "A5_A5") (pintype "bidirectional"))
    )
    (net (code "63") (name "unconnected-(U2-PadAREF)") (class "Default")
      (node (ref "U2") (pin "AREF") (pinfunction "AREF_AREF") (pintype "bidirectional"))
    )
    (net (code "64") (name "unconnected-(U2-PadIOREF)") (class "Default")
      (node (ref "U2") (pin "IOREF") (pinfunction "IOREF_IOREF") (pintype "bidirectional"))
    )
    (net (code "65") (name "unconnected-(U2-PadRX)") (class "Default")
      (node (ref "U2") (pin "RX") (pinfunction "RX_RX") (pintype "bidirectional"))
    )
    (net (code "66") (name "unconnected-(U2-PadSCL)") (class "Default")
      (node (ref "U2") (pin "SCL") (pinfunction "SCL_SCL") (pintype "bidirectional"))
    )
    (net (code "67") (name "unconnected-(U2-PadSDA)") (class "Default")
      (node (ref "U2") (pin "SDA") (pinfunction "SDA_SDA") (pintype "bidirectional"))
    )
    (net (code "68") (name "unconnected-(U2-PadTX)") (class "Default")
      (node (ref "U2") (pin "TX") (pinfunction "TX_TX") (pintype "bidirectional"))
    )
    (net (code "69") (name "unconnected-(U2-PadVIN)") (class "Default")
      (node (ref "U2") (pin "VIN") (pinfunction "VIN_VIN") (pintype "bidirectional"))
    )
    (net (code "70") (name "unconnected-(U3-LINEIN-Pad48)") (class "Default")
      (node (ref "U3") (pin "48") (pinfunction "LINEIN_48") (pintype "bidirectional"))
    )
    (net (code "71") (name "unconnected-(U3-MICN-Pad2)") (class "Default")
      (node (ref "U3") (pin "2") (pinfunction "MICN_2") (pintype "bidirectional"))
    )
    (net (code "72") (name "unconnected-(U3-MICP-Pad1)") (class "Default")
      (node (ref "U3") (pin "1") (pinfunction "MICP_1") (pintype "bidirectional"))
    )
    (net (code "73") (name "unconnected-(U3-TX-Pad27)") (class "Default")
      (node (ref "U3") (pin "27") (pinfunction "TX_27") (pintype "bidirectional"))
    )
    (net (code "74") (name "unconnected-(U3-VCO-Pad15)") (class "Default")
      (node (ref "U3") (pin "15") (pinfunction "VCO_15") (pintype "bidirectional"))
    )
    (net (code "75") (name "unconnected-(U4-BP-Pad4)") (class "Default")
      (node (ref "U4") (pin "4") (pinfunction "BP_4") (pintype "input"))
    )
    (net (code "76") (name "unconnected-(U6-NC-Pad1)") (class "Default")
      (node (ref "U6") (pin "1") (pinfunction "NC_1") (pintype "bidirectional"))
    )
    (net (code "77") (name "unconnected-(U6-RSV-Pad8)") (class "Default")
      (node (ref "U6") (pin "8") (pinfunction "RSV_8") (pintype "bidirectional"))
    )
    (net (code "78") (name "{slash}MUTE") (class "Default")
      (node (ref "R17") (pin "1") (pinfunction "1_1") (pintype "passive"))
      (node (ref "R19") (pin "1") (pinfunction "1_1") (pintype "passive"))
      (node (ref "R23") (pin "1") (pinfunction "1_1") (pintype "passive"))
      (node (ref "R24") (pin "2") (pinfunction "2_2") (pintype "passive"))
    )
  )
)
